# TF0060DCA.net
KiCad netlist of a schematic drawn in EAGLE
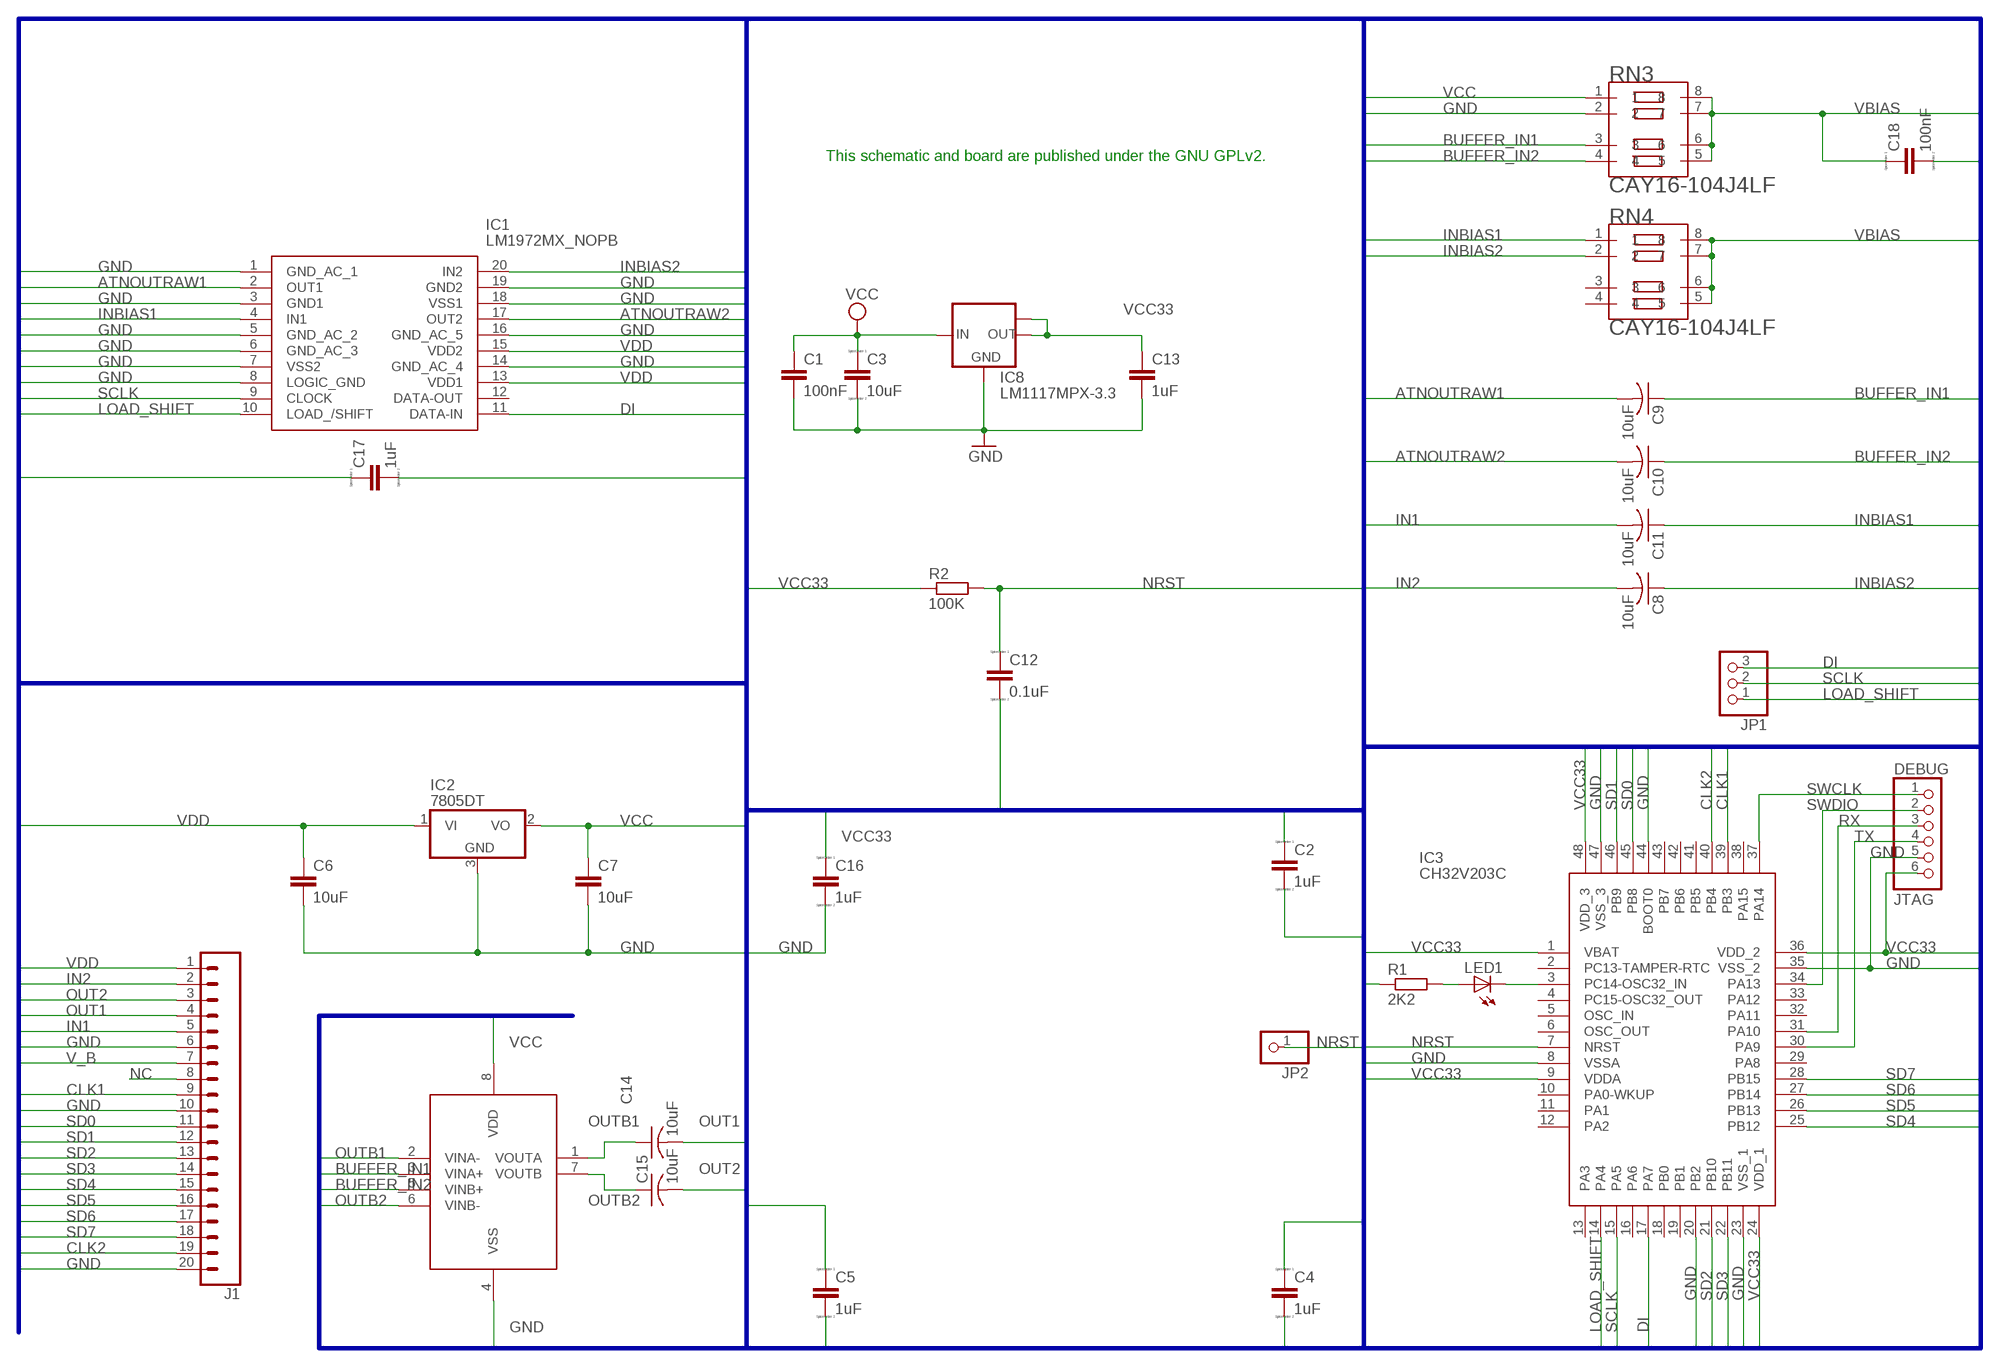
[diagram p0: schematic, sheet 1]

(export (version "E")
  (design (tool "Eeschema 10.0.6"))
  (components
    (comp (ref "C1")
      (value "100nF")
      (footprint "eagle-import:C1206")
      (libsource (lib "eagle-import") (part "C-EUC1206"))
    )
    (comp (ref "C2")
      (value "1uF")
      (footprint "eagle-import:C0603")
      (libsource (lib "eagle-import") (part "CC0603"))
    )
    (comp (ref "C3")
      (value "10uF")
      (footprint "eagle-import:C0603")
      (libsource (lib "eagle-import") (part "CC0603"))
    )
    (comp (ref "C4")
      (value "1uF")
      (footprint "eagle-import:C0603")
      (libsource (lib "eagle-import") (part "CC0603"))
    )
    (comp (ref "C5")
      (value "1uF")
      (footprint "eagle-import:C0603")
      (libsource (lib "eagle-import") (part "CC0603"))
    )
    (comp (ref "C6")
      (value "10uF")
      (footprint "eagle-import:C1206")
      (libsource (lib "eagle-import") (part "C-EUC1206"))
    )
    (comp (ref "C7")
      (value "10uF")
      (footprint "eagle-import:C1206")
      (libsource (lib "eagle-import") (part "C-EUC1206"))
    )
    (comp (ref "C8")
      (value "10uF")
      (footprint "eagle-import:C0805")
      (libsource (lib "eagle-import") (part "C-USC0805"))
    )
    (comp (ref "C9")
      (value "10uF")
      (footprint "eagle-import:C0805")
      (libsource (lib "eagle-import") (part "C-USC0805"))
    )
    (comp (ref "C10")
      (value "10uF")
      (footprint "eagle-import:C0805")
      (libsource (lib "eagle-import") (part "C-USC0805"))
    )
    (comp (ref "C11")
      (value "10uF")
      (footprint "eagle-import:C0805")
      (libsource (lib "eagle-import") (part "C-USC0805"))
    )
    (comp (ref "C12")
      (value "0.1uF")
      (footprint "eagle-import:C0603")
      (libsource (lib "eagle-import") (part "CC0603"))
    )
    (comp (ref "C13")
      (value "1uF")
      (footprint "eagle-import:C1206")
      (libsource (lib "eagle-import") (part "C-EUC1206"))
    )
    (comp (ref "C14")
      (value "10uF")
      (footprint "eagle-import:C0805")
      (libsource (lib "eagle-import") (part "C-USC0805"))
    )
    (comp (ref "C15")
      (value "10uF")
      (footprint "eagle-import:C0805")
      (libsource (lib "eagle-import") (part "C-USC0805"))
    )
    (comp (ref "C16")
      (value "1uF")
      (footprint "eagle-import:C0603")
      (libsource (lib "eagle-import") (part "CC0603"))
    )
    (comp (ref "C17")
      (value "1uF")
      (footprint "eagle-import:C0603")
      (libsource (lib "eagle-import") (part "CC0603"))
    )
    (comp (ref "C18")
      (value "100nF")
      (footprint "eagle-import:C0603")
      (libsource (lib "eagle-import") (part "CC0603"))
    )
    (comp (ref "DEBUG")
      (value "JTAG")
      (footprint "eagle-import:1X06_ROUND")
      (libsource (lib "eagle-import") (part "HEADER-1X6ROUND"))
    )
    (comp (ref "IC1")
      (value "LM1972MX_NOPB")
      (footprint "eagle-import:SOIC127P1030X265-20N")
      (fields
        (field (name "MANUFACTURER_PART_NUMBER") "LM1972MX/NOPB")
        (field (name "MOUSER_PART_NUMBER") "926-LM1972MX/NOPB")
      )
      (libsource (lib "eagle-import") (part "LM1972MX_NOPB"))
    )
    (comp (ref "IC2")
      (value "7805DT")
      (footprint "eagle-import:TO252")
      (libsource (lib "eagle-import") (part "78DT05"))
    )
    (comp (ref "IC3")
      (value "CH32V203C")
      (footprint "eagle-import:QFP50P900X900X160-48N")
      (fields
        (field (name "MANUFACTURER_PART_NUMBER") "STM32F103CBT6")
        (field (name "MOUSER_PART_NUMBER") "511-STM32F103CBT6")
      )
      (libsource (lib "eagle-import") (part "STM32F103CBT6"))
    )
    (comp (ref "IC8")
      (value "LM1117MPX-3.3")
      (footprint "eagle-import:SOT223")
      (libsource (lib "eagle-import") (part "LM1117MPX-3.3"))
    )
    (comp (ref "IC12")
      (value "MCP6002T-I_SN")
      (footprint "eagle-import:SOIC127P600X175-8N")
      (fields
        (field (name "MANUFACTURER_PART_NUMBER") "MCP6002T-I/SN")
        (field (name "RS_PART_NUMBER") "8234276P")
      )
      (libsource (lib "eagle-import") (part "MCP6002T-I_SN"))
    )
    (comp (ref "J1")
      (value "CONN_20")
      (footprint "eagle-import:1X20")
      (libsource (lib "eagle-import") (part "CONN_20"))
    )
    (comp (ref "JP1")
      (value "PINHD-1X3")
      (footprint "eagle-import:1X03")
      (libsource (lib "eagle-import") (part "PINHD-1X3"))
    )
    (comp (ref "JP2")
      (value "PINHD-1X1")
      (footprint "eagle-import:1X01")
      (libsource (lib "eagle-import") (part "PINHD-1X1"))
    )
    (comp (ref "LED1")
      (value "LEDCHIPLED_0603")
      (footprint "eagle-import:CHIPLED_0603")
      (libsource (lib "eagle-import") (part "LEDCHIPLED_0603"))
    )
    (comp (ref "R1")
      (value "2K2")
      (footprint "eagle-import:R0603")
      (libsource (lib "eagle-import") (part "R-EU_R0603"))
    )
    (comp (ref "R2")
      (value "100K")
      (footprint "eagle-import:R0603")
      (libsource (lib "eagle-import") (part "R-EU_R0603"))
    )
    (comp (ref "RN3")
      (value "CAY16-104J4LF")
      (footprint "eagle-import:RESCAXE80P320X160-8N")
      (fields (field (name "MF") "Bourns") (field (name "MP") "CAY16-103J4LF"))
      (libsource (lib "eagle-import") (part "CAY16-103J4LF"))
    )
    (comp (ref "RN4")
      (value "CAY16-104J4LF")
      (footprint "eagle-import:RESCAXE80P320X160-8N")
      (fields (field (name "MF") "Bourns") (field (name "MP") "CAY16-103J4LF"))
      (libsource (lib "eagle-import") (part "CAY16-103J4LF"))
    )
  )
  (nets
    (net (code "1") (name "/ATNOUTRAW1") (class "Default")
      (node (ref "C9") (pin "2") (pinfunction "2_2") (pintype "passive"))
      (node (ref "IC1") (pin "2") (pinfunction "OUT1_2") (pintype "bidirectional"))
    )
    (net (code "2") (name "/ATNOUTRAW2") (class "Default")
      (node (ref "C10") (pin "2") (pinfunction "2_2") (pintype "passive"))
      (node (ref "IC1") (pin "17") (pinfunction "OUT2_17") (pintype "bidirectional"))
    )
    (net (code "3") (name "/BUFFER_IN1") (class "Default")
      (node (ref "C9") (pin "1") (pinfunction "1_1") (pintype "passive"))
      (node (ref "IC12") (pin "3") (pinfunction "VINA+_3") (pintype "bidirectional"))
      (node (ref "RN3") (pin "3") (pinfunction "3_3") (pintype "passive"))
    )
    (net (code "4") (name "/BUFFER_IN2") (class "Default")
      (node (ref "C10") (pin "1") (pinfunction "1_1") (pintype "passive"))
      (node (ref "IC12") (pin "5") (pinfunction "VINB+_5") (pintype "bidirectional"))
      (node (ref "RN3") (pin "4") (pinfunction "4_4") (pintype "passive"))
    )
    (net (code "5") (name "/CLK1") (class "Default")
      (node (ref "IC3") (pin "39") (pinfunction "PB3_39") (pintype "bidirectional"))
      (node (ref "J1") (pin "9") (pinfunction "9_9") (pintype "passive"))
    )
    (net (code "6") (name "/CLK2") (class "Default")
      (node (ref "IC3") (pin "40") (pinfunction "PB4_40") (pintype "bidirectional"))
      (node (ref "J1") (pin "19") (pinfunction "19_19") (pintype "passive"))
    )
    (net (code "7") (name "/DI") (class "Default")
      (node (ref "IC1") (pin "11") (pinfunction "DATA-IN_11") (pintype "bidirectional"))
      (node (ref "IC3") (pin "17") (pinfunction "PA7_17") (pintype "bidirectional"))
      (node (ref "JP1") (pin "3") (pinfunction "3_3") (pintype "passive"))
    )
    (net (code "8") (name "/IN1") (class "Default")
      (node (ref "C11") (pin "2") (pinfunction "2_2") (pintype "passive"))
      (node (ref "J1") (pin "5") (pinfunction "5_5") (pintype "passive"))
    )
    (net (code "9") (name "/IN2") (class "Default")
      (node (ref "C8") (pin "2") (pinfunction "2_2") (pintype "passive"))
      (node (ref "J1") (pin "2") (pinfunction "2_2") (pintype "passive"))
    )
    (net (code "10") (name "/INBIAS1") (class "Default")
      (node (ref "C11") (pin "1") (pinfunction "1_1") (pintype "passive"))
      (node (ref "IC1") (pin "4") (pinfunction "IN1_4") (pintype "bidirectional"))
      (node (ref "RN4") (pin "1") (pinfunction "1_1") (pintype "passive"))
    )
    (net (code "11") (name "/INBIAS2") (class "Default")
      (node (ref "C8") (pin "1") (pinfunction "1_1") (pintype "passive"))
      (node (ref "IC1") (pin "20") (pinfunction "IN2_20") (pintype "bidirectional"))
      (node (ref "RN4") (pin "2") (pinfunction "2_2") (pintype "passive"))
    )
    (net (code "12") (name "/LOAD_SHIFT") (class "Default")
      (node (ref "IC1") (pin "10") (pinfunction "LOAD_/SHIFT_10") (pintype "bidirectional"))
      (node (ref "IC3") (pin "14") (pinfunction "PA4_14") (pintype "bidirectional"))
      (node (ref "JP1") (pin "1") (pinfunction "1_1") (pintype "passive"))
    )
    (net (code "13") (name "/NC") (class "Default")
      (node (ref "J1") (pin "8") (pinfunction "8_8") (pintype "passive"))
    )
    (net (code "14") (name "/NRST") (class "Default")
      (node (ref "C12") (pin "1") (pinfunction "1_1") (pintype "passive"))
      (node (ref "IC3") (pin "7") (pinfunction "NRST_7") (pintype "bidirectional"))
      (node (ref "JP2") (pin "1") (pinfunction "1_1") (pintype "passive"))
      (node (ref "R2") (pin "2") (pinfunction "2_2") (pintype "passive"))
    )
    (net (code "15") (name "/OUT1") (class "Default")
      (node (ref "C14") (pin "2") (pinfunction "2_2") (pintype "passive"))
      (node (ref "J1") (pin "4") (pinfunction "4_4") (pintype "passive"))
    )
    (net (code "16") (name "/OUT2") (class "Default")
      (node (ref "C15") (pin "2") (pinfunction "2_2") (pintype "passive"))
      (node (ref "J1") (pin "3") (pinfunction "3_3") (pintype "passive"))
    )
    (net (code "17") (name "/OUTB1") (class "Default")
      (node (ref "C14") (pin "1") (pinfunction "1_1") (pintype "passive"))
      (node (ref "IC12") (pin "1") (pinfunction "VOUTA_1") (pintype "bidirectional"))
      (node (ref "IC12") (pin "2") (pinfunction "VINA-_2") (pintype "bidirectional"))
    )
    (net (code "18") (name "/OUTB2") (class "Default")
      (node (ref "C15") (pin "1") (pinfunction "1_1") (pintype "passive"))
      (node (ref "IC12") (pin "6") (pinfunction "VINB-_6") (pintype "bidirectional"))
      (node (ref "IC12") (pin "7") (pinfunction "VOUTB_7") (pintype "bidirectional"))
    )
    (net (code "19") (name "/RX") (class "Default")
      (node (ref "DEBUG") (pin "3") (pinfunction "3_3") (pintype "passive"))
      (node (ref "IC3") (pin "31") (pinfunction "PA10_31") (pintype "bidirectional"))
    )
    (net (code "20") (name "/SCLK") (class "Default")
      (node (ref "IC1") (pin "9") (pinfunction "CLOCK_9") (pintype "bidirectional"))
      (node (ref "IC3") (pin "15") (pinfunction "PA5_15") (pintype "bidirectional"))
      (node (ref "JP1") (pin "2") (pinfunction "2_2") (pintype "passive"))
    )
    (net (code "21") (name "/SD0") (class "Default")
      (node (ref "IC3") (pin "45") (pinfunction "PB8_45") (pintype "bidirectional"))
      (node (ref "J1") (pin "11") (pinfunction "11_11") (pintype "passive"))
    )
    (net (code "22") (name "/SD1") (class "Default")
      (node (ref "IC3") (pin "46") (pinfunction "PB9_46") (pintype "bidirectional"))
      (node (ref "J1") (pin "12") (pinfunction "12_12") (pintype "passive"))
    )
    (net (code "23") (name "/SD2") (class "Default")
      (node (ref "IC3") (pin "21") (pinfunction "PB10_21") (pintype "bidirectional"))
      (node (ref "J1") (pin "13") (pinfunction "13_13") (pintype "passive"))
    )
    (net (code "24") (name "/SD3") (class "Default")
      (node (ref "IC3") (pin "22") (pinfunction "PB11_22") (pintype "bidirectional"))
      (node (ref "J1") (pin "14") (pinfunction "14_14") (pintype "passive"))
    )
    (net (code "25") (name "/SD4") (class "Default")
      (node (ref "IC3") (pin "25") (pinfunction "PB12_25") (pintype "bidirectional"))
      (node (ref "J1") (pin "15") (pinfunction "15_15") (pintype "passive"))
    )
    (net (code "26") (name "/SD5") (class "Default")
      (node (ref "IC3") (pin "26") (pinfunction "PB13_26") (pintype "bidirectional"))
      (node (ref "J1") (pin "16") (pinfunction "16_16") (pintype "passive"))
    )
    (net (code "27") (name "/SD6") (class "Default")
      (node (ref "IC3") (pin "27") (pinfunction "PB14_27") (pintype "bidirectional"))
      (node (ref "J1") (pin "17") (pinfunction "17_17") (pintype "passive"))
    )
    (net (code "28") (name "/SD7") (class "Default")
      (node (ref "IC3") (pin "28") (pinfunction "PB15_28") (pintype "bidirectional"))
      (node (ref "J1") (pin "18") (pinfunction "18_18") (pintype "passive"))
    )
    (net (code "29") (name "/SWCLK") (class "Default")
      (node (ref "DEBUG") (pin "1") (pinfunction "1_1") (pintype "passive"))
      (node (ref "IC3") (pin "37") (pinfunction "PA14_37") (pintype "bidirectional"))
    )
    (net (code "30") (name "/SWDIO") (class "Default")
      (node (ref "DEBUG") (pin "2") (pinfunction "2_2") (pintype "passive"))
      (node (ref "IC3") (pin "34") (pinfunction "PA13_34") (pintype "bidirectional"))
    )
    (net (code "31") (name "/TX") (class "Default")
      (node (ref "DEBUG") (pin "4") (pinfunction "4_4") (pintype "passive"))
      (node (ref "IC3") (pin "30") (pinfunction "PA9_30") (pintype "bidirectional"))
    )
    (net (code "32") (name "/VBIAS") (class "Default")
      (node (ref "C18") (pin "1") (pinfunction "1_1") (pintype "passive"))
      (node (ref "RN3") (pin "5") (pinfunction "5_5") (pintype "passive"))
      (node (ref "RN3") (pin "6") (pinfunction "6_6") (pintype "passive"))
      (node (ref "RN3") (pin "7") (pinfunction "7_7") (pintype "passive"))
      (node (ref "RN3") (pin "8") (pinfunction "8_8") (pintype "passive"))
      (node (ref "RN4") (pin "5") (pinfunction "5_5") (pintype "passive"))
      (node (ref "RN4") (pin "6") (pinfunction "6_6") (pintype "passive"))
      (node (ref "RN4") (pin "7") (pinfunction "7_7") (pintype "passive"))
      (node (ref "RN4") (pin "8") (pinfunction "8_8") (pintype "passive"))
    )
    (net (code "33") (name "/VCC33") (class "Default")
      (node (ref "C13") (pin "1") (pinfunction "1_1") (pintype "passive"))
      (node (ref "C16") (pin "1") (pinfunction "1_1") (pintype "passive"))
      (node (ref "C2") (pin "1") (pinfunction "1_1") (pintype "passive"))
      (node (ref "C4") (pin "1") (pinfunction "1_1") (pintype "passive"))
      (node (ref "C5") (pin "1") (pinfunction "1_1") (pintype "passive"))
      (node (ref "DEBUG") (pin "6") (pinfunction "6_6") (pintype "passive"))
      (node (ref "IC3") (pin "1") (pinfunction "VBAT_1") (pintype "bidirectional"))
      (node (ref "IC3") (pin "24") (pinfunction "VDD_1_24") (pintype "bidirectional"))
      (node (ref "IC3") (pin "36") (pinfunction "VDD_2_36") (pintype "bidirectional"))
      (node (ref "IC3") (pin "48") (pinfunction "VDD_3_48") (pintype "bidirectional"))
      (node (ref "IC3") (pin "9") (pinfunction "VDDA_9") (pintype "bidirectional"))
      (node (ref "IC8") (pin "2") (pinfunction "OUT_2") (pintype "passive"))
      (node (ref "IC8") (pin "TAB") (pinfunction "OUT1_TAB") (pintype "passive"))
      (node (ref "R1") (pin "1") (pinfunction "1_1") (pintype "passive"))
      (node (ref "R2") (pin "1") (pinfunction "1_1") (pintype "passive"))
    )
    (net (code "34") (name "/VDD") (class "Default")
      (node (ref "C6") (pin "1") (pinfunction "1_1") (pintype "passive"))
      (node (ref "IC1") (pin "13") (pinfunction "VDD1_13") (pintype "bidirectional"))
      (node (ref "IC1") (pin "15") (pinfunction "VDD2_15") (pintype "bidirectional"))
      (node (ref "IC2") (pin "1") (pinfunction "VI_1") (pintype "input"))
      (node (ref "J1") (pin "1") (pinfunction "1_1") (pintype "passive"))
    )
    (net (code "35") (name "/V_B") (class "Default")
      (node (ref "J1") (pin "7") (pinfunction "7_7") (pintype "passive"))
    )
    (net (code "36") (name "GND") (class "Default")
      (node (ref "C1") (pin "2") (pinfunction "2_2") (pintype "passive"))
      (node (ref "C12") (pin "2") (pinfunction "2_2") (pintype "passive"))
      (node (ref "C13") (pin "2") (pinfunction "2_2") (pintype "passive"))
      (node (ref "C16") (pin "2") (pinfunction "2_2") (pintype "passive"))
      (node (ref "C17") (pin "2") (pinfunction "2_2") (pintype "passive"))
      (node (ref "C18") (pin "2") (pinfunction "2_2") (pintype "passive"))
      (node (ref "C2") (pin "2") (pinfunction "2_2") (pintype "passive"))
      (node (ref "C3") (pin "2") (pinfunction "2_2") (pintype "passive"))
      (node (ref "C4") (pin "2") (pinfunction "2_2") (pintype "passive"))
      (node (ref "C5") (pin "2") (pinfunction "2_2") (pintype "passive"))
      (node (ref "C6") (pin "2") (pinfunction "2_2") (pintype "passive"))
      (node (ref "C7") (pin "2") (pinfunction "2_2") (pintype "passive"))
      (node (ref "DEBUG") (pin "5") (pinfunction "5_5") (pintype "passive"))
      (node (ref "IC1") (pin "1") (pinfunction "GND_AC_1_1") (pintype "bidirectional"))
      (node (ref "IC1") (pin "14") (pinfunction "GND_AC_4_14") (pintype "bidirectional"))
      (node (ref "IC1") (pin "16") (pinfunction "GND_AC_5_16") (pintype "bidirectional"))
      (node (ref "IC1") (pin "18") (pinfunction "VSS1_18") (pintype "bidirectional"))
      (node (ref "IC1") (pin "19") (pinfunction "GND2_19") (pintype "bidirectional"))
      (node (ref "IC1") (pin "3") (pinfunction "GND1_3") (pintype "bidirectional"))
      (node (ref "IC1") (pin "5") (pinfunction "GND_AC_2_5") (pintype "bidirectional"))
      (node (ref "IC1") (pin "6") (pinfunction "GND_AC_3_6") (pintype "bidirectional"))
      (node (ref "IC1") (pin "7") (pinfunction "VSS2_7") (pintype "bidirectional"))
      (node (ref "IC1") (pin "8") (pinfunction "LOGIC_GND_8") (pintype "bidirectional"))
      (node (ref "IC12") (pin "4") (pinfunction "VSS_4") (pintype "bidirectional"))
      (node (ref "IC2") (pin "3") (pinfunction "GND_3") (pintype "passive"))
      (node (ref "IC3") (pin "20") (pinfunction "PB2_20") (pintype "bidirectional"))
      (node (ref "IC3") (pin "23") (pinfunction "VSS_1_23") (pintype "bidirectional"))
      (node (ref "IC3") (pin "35") (pinfunction "VSS_2_35") (pintype "bidirectional"))
      (node (ref "IC3") (pin "44") (pinfunction "BOOT0_44") (pintype "bidirectional"))
      (node (ref "IC3") (pin "47") (pinfunction "VSS_3_47") (pintype "bidirectional"))
      (node (ref "IC3") (pin "8") (pinfunction "VSSA_8") (pintype "bidirectional"))
      (node (ref "IC8") (pin "1") (pinfunction "GND_1") (pintype "input"))
      (node (ref "J1") (pin "10") (pinfunction "10_10") (pintype "passive"))
      (node (ref "J1") (pin "20") (pinfunction "20_20") (pintype "passive"))
      (node (ref "J1") (pin "6") (pinfunction "6_6") (pintype "passive"))
      (node (ref "RN3") (pin "2") (pinfunction "2_2") (pintype "passive"))
    )
    (net (code "37") (name "Net-(IC3-PC14-OSC32_IN)") (class "Default")
      (node (ref "IC3") (pin "3") (pinfunction "PC14-OSC32_IN_3") (pintype "bidirectional"))
      (node (ref "LED1") (pin "C") (pinfunction "C_C") (pintype "passive"))
    )
    (net (code "38") (name "Net-(LED1-PadA)") (class "Default")
      (node (ref "LED1") (pin "A") (pinfunction "A_A") (pintype "passive"))
      (node (ref "R1") (pin "2") (pinfunction "2_2") (pintype "passive"))
    )
    (net (code "39") (name "VCC") (class "Default")
      (node (ref "C1") (pin "1") (pinfunction "1_1") (pintype "passive"))
      (node (ref "C17") (pin "1") (pinfunction "1_1") (pintype "passive"))
      (node (ref "C3") (pin "1") (pinfunction "1_1") (pintype "passive"))
      (node (ref "C7") (pin "1") (pinfunction "1_1") (pintype "passive"))
      (node (ref "IC12") (pin "8") (pinfunction "VDD_8") (pintype "bidirectional"))
      (node (ref "IC2") (pin "2") (pinfunction "VO_2") (pintype "passive"))
      (node (ref "IC8") (pin "3") (pinfunction "IN_3") (pintype "input"))
      (node (ref "RN3") (pin "1") (pinfunction "1_1") (pintype "passive"))
    )
    (net (code "40") (name "unconnected-(IC1-DATA-OUT-Pad12)") (class "Default")
      (node (ref "IC1") (pin "12") (pinfunction "DATA-OUT_12") (pintype "bidirectional"))
    )
    (net (code "41") (name "unconnected-(IC3-OSC_IN-Pad5)") (class "Default")
      (node (ref "IC3") (pin "5") (pinfunction "OSC_IN_5") (pintype "bidirectional"))
    )
    (net (code "42") (name "unconnected-(IC3-OSC_OUT-Pad6)") (class "Default")
      (node (ref "IC3") (pin "6") (pinfunction "OSC_OUT_6") (pintype "bidirectional"))
    )
    (net (code "43") (name "unconnected-(IC3-PA0-WKUP-Pad10)") (class "Default")
      (node (ref "IC3") (pin "10") (pinfunction "PA0-WKUP_10") (pintype "bidirectional"))
    )
    (net (code "44") (name "unconnected-(IC3-PA1-Pad11)") (class "Default")
      (node (ref "IC3") (pin "11") (pinfunction "PA1_11") (pintype "bidirectional"))
    )
    (net (code "45") (name "unconnected-(IC3-PA2-Pad12)") (class "Default")
      (node (ref "IC3") (pin "12") (pinfunction "PA2_12") (pintype "bidirectional"))
    )
    (net (code "46") (name "unconnected-(IC3-PA3-Pad13)") (class "Default")
      (node (ref "IC3") (pin "13") (pinfunction "PA3_13") (pintype "bidirectional"))
    )
    (net (code "47") (name "unconnected-(IC3-PA6-Pad16)") (class "Default")
      (node (ref "IC3") (pin "16") (pinfunction "PA6_16") (pintype "bidirectional"))
    )
    (net (code "48") (name "unconnected-(IC3-PA8-Pad29)") (class "Default")
      (node (ref "IC3") (pin "29") (pinfunction "PA8_29") (pintype "bidirectional"))
    )
    (net (code "49") (name "unconnected-(IC3-PA11-Pad32)") (class "Default")
      (node (ref "IC3") (pin "32") (pinfunction "PA11_32") (pintype "bidirectional"))
    )
    (net (code "50") (name "unconnected-(IC3-PA12-Pad33)") (class "Default")
      (node (ref "IC3") (pin "33") (pinfunction "PA12_33") (pintype "bidirectional"))
    )
    (net (code "51") (name "unconnected-(IC3-PA15-Pad38)") (class "Default")
      (node (ref "IC3") (pin "38") (pinfunction "PA15_38") (pintype "bidirectional"))
    )
    (net (code "52") (name "unconnected-(IC3-PB0-Pad18)") (class "Default")
      (node (ref "IC3") (pin "18") (pinfunction "PB0_18") (pintype "bidirectional"))
    )
    (net (code "53") (name "unconnected-(IC3-PB1-Pad19)") (class "Default")
      (node (ref "IC3") (pin "19") (pinfunction "PB1_19") (pintype "bidirectional"))
    )
    (net (code "54") (name "unconnected-(IC3-PB5-Pad41)") (class "Default")
      (node (ref "IC3") (pin "41") (pinfunction "PB5_41") (pintype "bidirectional"))
    )
    (net (code "55") (name "unconnected-(IC3-PB6-Pad42)") (class "Default")
      (node (ref "IC3") (pin "42") (pinfunction "PB6_42") (pintype "bidirectional"))
    )
    (net (code "56") (name "unconnected-(IC3-PB7-Pad43)") (class "Default")
      (node (ref "IC3") (pin "43") (pinfunction "PB7_43") (pintype "bidirectional"))
    )
    (net (code "57") (name "unconnected-(IC3-PC13-TAMPER-RTC-Pad2)") (class "Default")
      (node (ref "IC3") (pin "2") (pinfunction "PC13-TAMPER-RTC_2") (pintype "bidirectional"))
    )
    (net (code "58") (name "unconnected-(IC3-PC15-OSC32_OUT-Pad4)") (class "Default")
      (node (ref "IC3") (pin "4") (pinfunction "PC15-OSC32_OUT_4") (pintype "bidirectional"))
    )
    (net (code "59") (name "unconnected-(RN4-Pad3)") (class "Default")
      (node (ref "RN4") (pin "3") (pinfunction "3_3") (pintype "passive"))
    )
    (net (code "60") (name "unconnected-(RN4-Pad4)") (class "Default")
      (node (ref "RN4") (pin "4") (pinfunction "4_4") (pintype "passive"))
    )
  )
)
